# ledecorator-core-board.net
KiCad netlist of a schematic drawn in EAGLE
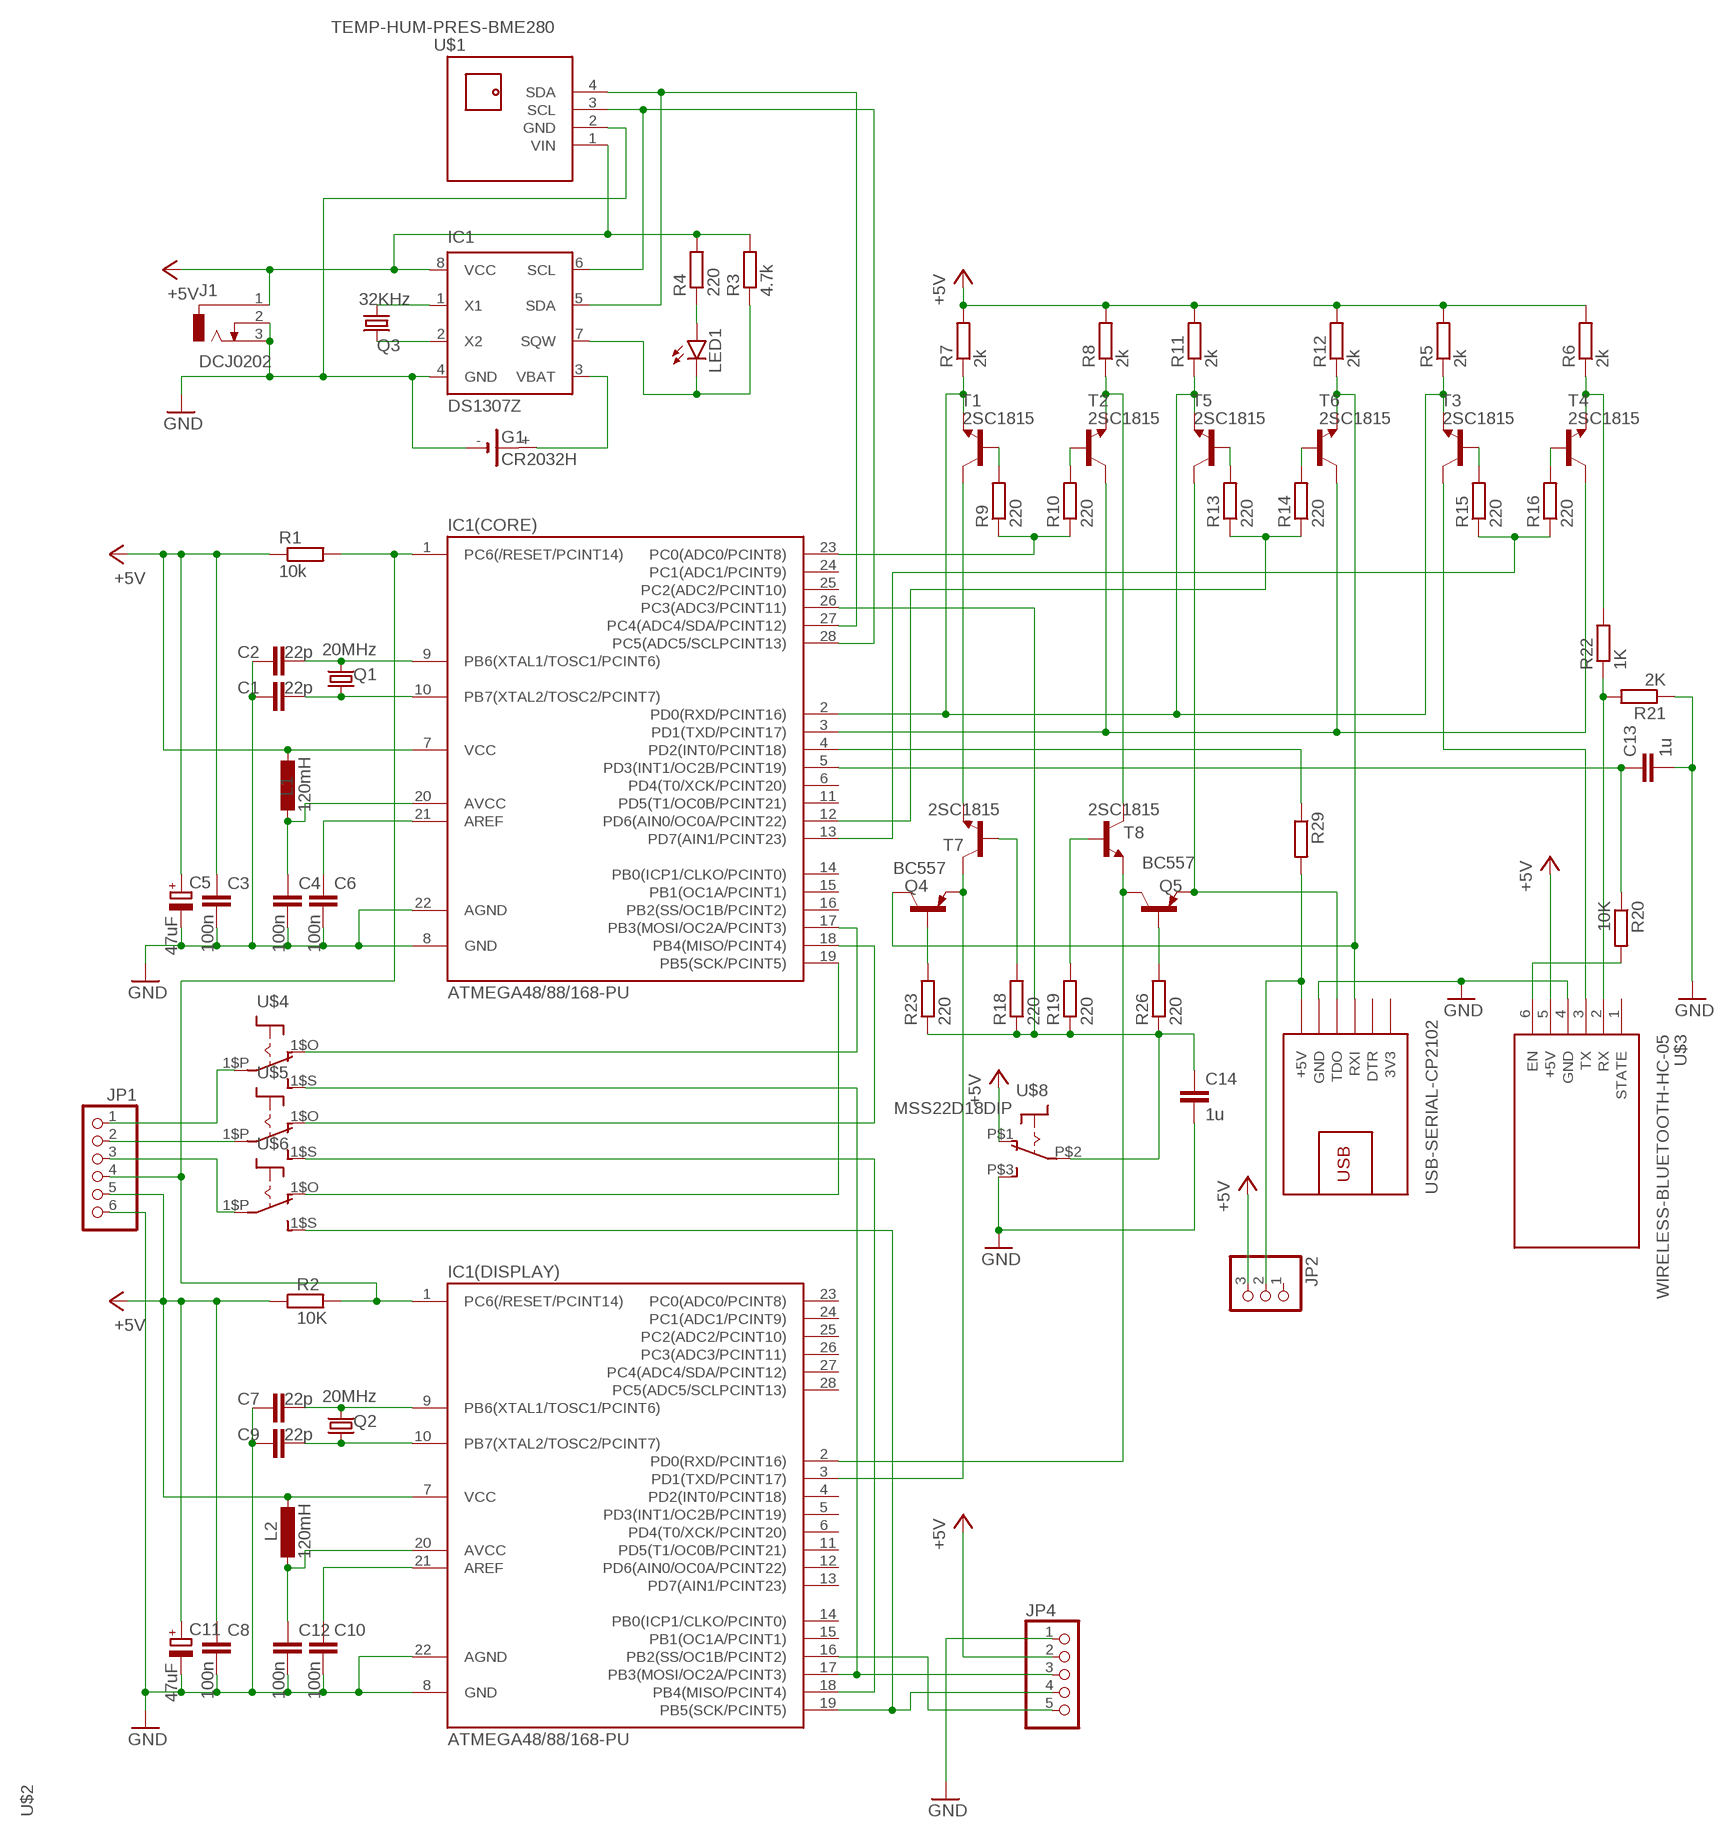
[diagram p0: schematic, sheet 1]

(export (version "E")
  (design (tool "Eeschema 10.0.6"))
  (components
    (comp (ref "C1")
      (value "22p")
      (footprint "eagle-import:C025-025X050")
      (libsource (lib "eagle-import") (part "C-EU025-025X050"))
    )
    (comp (ref "C2")
      (value "22p")
      (footprint "eagle-import:C025-025X050")
      (libsource (lib "eagle-import") (part "C-EU025-025X050"))
    )
    (comp (ref "C3")
      (value "100n")
      (footprint "eagle-import:C025-025X050")
      (libsource (lib "eagle-import") (part "C-EU025-025X050"))
    )
    (comp (ref "C4")
      (value "100n")
      (footprint "eagle-import:C1206")
      (libsource (lib "eagle-import") (part "C-EUC1206"))
    )
    (comp (ref "C5")
      (value "47uF")
      (footprint "eagle-import:E2-4")
      (libsource (lib "eagle-import") (part "CPOL-EUE2-4"))
    )
    (comp (ref "C6")
      (value "100n")
      (footprint "eagle-import:C1206")
      (libsource (lib "eagle-import") (part "C-EUC1206"))
    )
    (comp (ref "C7")
      (value "22p")
      (footprint "eagle-import:C025-025X050")
      (libsource (lib "eagle-import") (part "C-EU025-025X050"))
    )
    (comp (ref "C8")
      (value "100n")
      (footprint "eagle-import:C025-025X050")
      (libsource (lib "eagle-import") (part "C-EU025-025X050"))
    )
    (comp (ref "C9")
      (value "22p")
      (footprint "eagle-import:C025-025X050")
      (libsource (lib "eagle-import") (part "C-EU025-025X050"))
    )
    (comp (ref "C10")
      (value "100n")
      (footprint "eagle-import:C025-025X050")
      (libsource (lib "eagle-import") (part "C-EU025-025X050"))
    )
    (comp (ref "C11")
      (value "47uF")
      (footprint "eagle-import:E2-4")
      (libsource (lib "eagle-import") (part "CPOL-EUE2-4"))
    )
    (comp (ref "C12")
      (value "100n")
      (footprint "eagle-import:C025-025X050")
      (libsource (lib "eagle-import") (part "C-EU025-025X050"))
    )
    (comp (ref "C13")
      (value "1u")
      (footprint "eagle-import:C1206")
      (libsource (lib "eagle-import") (part "C-EUC1206"))
    )
    (comp (ref "C14")
      (value "1u")
      (footprint "eagle-import:C050-025X075")
      (libsource (lib "eagle-import") (part "C-EU050-025X075"))
    )
    (comp (ref "G1")
      (value "CR2032H")
      (footprint "eagle-import:CR2032H")
      (libsource (lib "eagle-import") (part "CR2032H"))
    )
    (comp (ref "IC1")
      (value "DS1307Z")
      (footprint "eagle-import:SOIC8")
      (libsource (lib "eagle-import") (part "DS1307Z"))
    )
    (comp (ref "IC1(CORE)")
      (value "ATMEGA48/88/168-PU")
      (footprint "eagle-import:DIL28-3")
      (libsource (lib "eagle-import") (part "ATMEGA48/88/168-PU"))
    )
    (comp (ref "IC1(DISPLAY)")
      (value "ATMEGA48/88/168-PU")
      (footprint "eagle-import:DIL28-3")
      (libsource (lib "eagle-import") (part "ATMEGA48/88/168-PU"))
    )
    (comp (ref "J1")
      (value "DCJ0202")
      (footprint "eagle-import:DCJ0202")
      (libsource (lib "eagle-import") (part "DCJ0202"))
    )
    (comp (ref "JP1")
      (value "PINHD-1X6/90")
      (footprint "eagle-import:1X06_90")
      (libsource (lib "eagle-import") (part "PINHD-1X6/90"))
    )
    (comp (ref "JP2")
      (value "PINHD-1X3/90")
      (footprint "eagle-import:1X03_90")
      (libsource (lib "eagle-import") (part "PINHD-1X3/90"))
    )
    (comp (ref "JP4")
      (value "PINHD-1X5")
      (footprint "eagle-import:1X05")
      (libsource (lib "eagle-import") (part "PINHD-1X5"))
    )
    (comp (ref "L1")
      (value "120mH")
      (footprint "eagle-import:0207_10")
      (libsource (lib "eagle-import") (part "L-EU0207/10"))
    )
    (comp (ref "L2")
      (value "120mH")
      (footprint "eagle-import:0207_10")
      (libsource (lib "eagle-import") (part "L-EU0207/10"))
    )
    (comp (ref "LED1")
      (value "LED3MM")
      (footprint "eagle-import:LED3MM")
      (libsource (lib "eagle-import") (part "LED3MM"))
    )
    (comp (ref "Q1")
      (value "20MHz")
      (footprint "eagle-import:HC49_S")
      (libsource (lib "eagle-import") (part "CRYSTALHC49S"))
    )
    (comp (ref "Q2")
      (value "20MHz")
      (footprint "eagle-import:HC49_S")
      (libsource (lib "eagle-import") (part "CRYSTALHC49S"))
    )
    (comp (ref "Q3")
      (value "32KHz")
      (footprint "eagle-import:TC26H")
      (libsource (lib "eagle-import") (part "CRYSTALTC26H"))
    )
    (comp (ref "Q4")
      (value "BC557")
      (footprint "eagle-import:TO92-EBC")
      (libsource (lib "eagle-import") (part "BC557"))
    )
    (comp (ref "Q5")
      (value "BC557")
      (footprint "eagle-import:TO92-EBC")
      (libsource (lib "eagle-import") (part "BC557"))
    )
    (comp (ref "R1")
      (value "10k")
      (footprint "eagle-import:0207_10")
      (libsource (lib "eagle-import") (part "rcl_334_R-EU_0207/10"))
    )
    (comp (ref "R2")
      (value "10K")
      (footprint "eagle-import:0207_10")
      (libsource (lib "eagle-import") (part "R-EU_0207/10"))
    )
    (comp (ref "R3")
      (value "4.7k")
      (footprint "eagle-import:R1206")
      (libsource (lib "eagle-import") (part "rcl_334_R-EU_R1206"))
    )
    (comp (ref "R4")
      (value "220")
      (footprint "eagle-import:R1206")
      (libsource (lib "eagle-import") (part "rcl_334_R-EU_R1206"))
    )
    (comp (ref "R5")
      (value "2k")
      (footprint "eagle-import:0207_12")
      (libsource (lib "eagle-import") (part "rcl_334_R-EU_0207/12"))
    )
    (comp (ref "R6")
      (value "2k")
      (footprint "eagle-import:0207_12")
      (libsource (lib "eagle-import") (part "rcl_334_R-EU_0207/12"))
    )
    (comp (ref "R7")
      (value "2k")
      (footprint "eagle-import:R1206")
      (libsource (lib "eagle-import") (part "rcl_334_R-EU_R1206"))
    )
    (comp (ref "R8")
      (value "2k")
      (footprint "eagle-import:R1206")
      (libsource (lib "eagle-import") (part "rcl_334_R-EU_R1206"))
    )
    (comp (ref "R9")
      (value "220")
      (footprint "eagle-import:0207_10")
      (libsource (lib "eagle-import") (part "rcl_334_R-EU_0207/10"))
    )
    (comp (ref "R10")
      (value "220")
      (footprint "eagle-import:0207_10")
      (libsource (lib "eagle-import") (part "rcl_334_R-EU_0207/10"))
    )
    (comp (ref "R11")
      (value "2k")
      (footprint "eagle-import:0207_12")
      (libsource (lib "eagle-import") (part "rcl_334_R-EU_0207/12"))
    )
    (comp (ref "R12")
      (value "2k")
      (footprint "eagle-import:0207_10")
      (libsource (lib "eagle-import") (part "rcl_334_R-EU_0207/10"))
    )
    (comp (ref "R13")
      (value "220")
      (footprint "eagle-import:0207_10")
      (libsource (lib "eagle-import") (part "rcl_334_R-EU_0207/10"))
    )
    (comp (ref "R14")
      (value "220")
      (footprint "eagle-import:0207_10")
      (libsource (lib "eagle-import") (part "rcl_334_R-EU_0207/10"))
    )
    (comp (ref "R15")
      (value "220")
      (footprint "eagle-import:0207_10")
      (libsource (lib "eagle-import") (part "rcl_334_R-EU_0207/10"))
    )
    (comp (ref "R16")
      (value "220")
      (footprint "eagle-import:0207_10")
      (libsource (lib "eagle-import") (part "rcl_334_R-EU_0207/10"))
    )
    (comp (ref "R18")
      (value "220")
      (footprint "eagle-import:0207_10")
      (libsource (lib "eagle-import") (part "rcl_334_R-EU_0207/10"))
    )
    (comp (ref "R19")
      (value "220")
      (footprint "eagle-import:0207_10")
      (libsource (lib "eagle-import") (part "rcl_334_R-EU_0207/10"))
    )
    (comp (ref "R20")
      (value "10K")
      (footprint "eagle-import:0207_10")
      (libsource (lib "eagle-import") (part "rcl_334_R-EU_0207/10"))
    )
    (comp (ref "R21")
      (value "2K")
      (footprint "eagle-import:0207_10")
      (libsource (lib "eagle-import") (part "rcl_334_R-EU_0207/10"))
    )
    (comp (ref "R22")
      (value "1K")
      (footprint "eagle-import:0207_10")
      (libsource (lib "eagle-import") (part "rcl_334_R-EU_0207/10"))
    )
    (comp (ref "R23")
      (value "220")
      (footprint "eagle-import:R1206")
      (libsource (lib "eagle-import") (part "rcl_334_R-EU_R1206"))
    )
    (comp (ref "R26")
      (value "220")
      (footprint "eagle-import:R1206")
      (libsource (lib "eagle-import") (part "rcl_334_R-EU_R1206"))
    )
    (comp (ref "R29")
      (value "R-EU_0207/10")
      (footprint "eagle-import:0207_10")
      (libsource (lib "eagle-import") (part "rcl_334_R-EU_0207/10"))
    )
    (comp (ref "T1")
      (value "2SC1815")
      (footprint "eagle-import:TO92-ECB")
      (libsource (lib "eagle-import") (part "2SC1815"))
    )
    (comp (ref "T2")
      (value "2SC1815")
      (footprint "eagle-import:TO92-ECB")
      (libsource (lib "eagle-import") (part "2SC1815"))
    )
    (comp (ref "T3")
      (value "2SC1815")
      (footprint "eagle-import:TO92-ECB")
      (libsource (lib "eagle-import") (part "2SC1815"))
    )
    (comp (ref "T4")
      (value "2SC1815")
      (footprint "eagle-import:TO92-ECB")
      (libsource (lib "eagle-import") (part "2SC1815"))
    )
    (comp (ref "T5")
      (value "2SC1815")
      (footprint "eagle-import:TO92-ECB")
      (libsource (lib "eagle-import") (part "2SC1815"))
    )
    (comp (ref "T6")
      (value "2SC1815")
      (footprint "eagle-import:TO92-ECB")
      (libsource (lib "eagle-import") (part "2SC1815"))
    )
    (comp (ref "T7")
      (value "2SC1815")
      (footprint "eagle-import:TO92-ECB")
      (libsource (lib "eagle-import") (part "2SC1815"))
    )
    (comp (ref "T8")
      (value "2SC1815")
      (footprint "eagle-import:TO92-ECB")
      (libsource (lib "eagle-import") (part "2SC1815"))
    )
    (comp (ref "U$1")
      (value "TEMP-HUM-PRES-BME280")
      (footprint "eagle-import:TEMP-HUM-PRES-BME280")
      (libsource (lib "eagle-import") (part "TEMP-HUM-PRES-BME280"))
    )
    (comp (ref "U$2")
      (value "USB-SERIAL-CP2102")
      (footprint "eagle-import:USB-SERIAL-CP2102")
      (libsource (lib "eagle-import") (part "USB-SERIAL-CP2102"))
    )
    (comp (ref "U$3")
      (value "WIRELESS-BLUETOOTH-HC-05")
      (footprint "eagle-import:WIRELESS-BLUETOOTH-HC-05")
      (libsource (lib "eagle-import") (part "WIRELESS-BLUETOOTH-HC-05"))
    )
    (comp (ref "U$4")
      (value "SS12D00DIP")
      (footprint "eagle-import:SS12D00")
      (libsource (lib "eagle-import") (part "SS12D00DIP"))
    )
    (comp (ref "U$5")
      (value "SS12D00DIP")
      (footprint "eagle-import:SS12D00")
      (libsource (lib "eagle-import") (part "SS12D00DIP"))
    )
    (comp (ref "U$6")
      (value "SS12D00DIP")
      (footprint "eagle-import:SS12D00")
      (libsource (lib "eagle-import") (part "SS12D00DIP"))
    )
    (comp (ref "U$8")
      (value "MSS22D18DIP")
      (footprint "eagle-import:MSS22D18")
      (libsource (lib "eagle-import") (part "MSS22D18DIP"))
    )
  )
  (nets
    (net (code "1") (name "+5V") (class "Default")
      (node (ref "C11") (pin "+") (pinfunction "+_+") (pintype "passive"))
      (node (ref "C3") (pin "1") (pinfunction "1_1") (pintype "passive"))
      (node (ref "C5") (pin "+") (pinfunction "+_+") (pintype "passive"))
      (node (ref "C8") (pin "1") (pinfunction "1_1") (pintype "passive"))
      (node (ref "IC1") (pin "8") (pinfunction "VCC_8") (pintype "power_in"))
      (node (ref "IC1(CORE)") (pin "7") (pinfunction "VCC_7") (pintype "power_in"))
      (node (ref "IC1(DISPLAY)") (pin "7") (pinfunction "VCC_7") (pintype "power_in"))
      (node (ref "J1") (pin "1") (pinfunction "1_1") (pintype "passive"))
      (node (ref "JP1") (pin "5") (pinfunction "5_5") (pintype "passive"))
      (node (ref "JP2") (pin "3") (pinfunction "3_3") (pintype "passive"))
      (node (ref "JP4") (pin "2") (pinfunction "2_2") (pintype "passive"))
      (node (ref "L1") (pin "1") (pinfunction "1_1") (pintype "passive"))
      (node (ref "L2") (pin "1") (pinfunction "1_1") (pintype "passive"))
      (node (ref "R1") (pin "1") (pinfunction "1_1") (pintype "passive"))
      (node (ref "R11") (pin "2") (pinfunction "2_2") (pintype "passive"))
      (node (ref "R12") (pin "2") (pinfunction "2_2") (pintype "passive"))
      (node (ref "R2") (pin "1") (pinfunction "1_1") (pintype "passive"))
      (node (ref "R3") (pin "2") (pinfunction "2_2") (pintype "passive"))
      (node (ref "R4") (pin "2") (pinfunction "2_2") (pintype "passive"))
      (node (ref "R5") (pin "2") (pinfunction "2_2") (pintype "passive"))
      (node (ref "R6") (pin "2") (pinfunction "2_2") (pintype "passive"))
      (node (ref "R7") (pin "2") (pinfunction "2_2") (pintype "passive"))
      (node (ref "R8") (pin "2") (pinfunction "2_2") (pintype "passive"))
      (node (ref "U$1") (pin "1") (pinfunction "VIN_1") (pintype "power_in"))
      (node (ref "U$3") (pin "5") (pinfunction "+5V_5") (pintype "power_in"))
      (node (ref "U$8") (pin "P$1") (pinfunction "O_P$1") (pintype "passive"))
    )
    (net (code "2") (name "/3V3") (class "Default")
      (node (ref "U$2") (pin "1") (pinfunction "3V3_1") (pintype "power_in"))
    )
    (net (code "3") (name "GND") (class "Default")
      (node (ref "C1") (pin "1") (pinfunction "1_1") (pintype "passive"))
      (node (ref "C10") (pin "2") (pinfunction "2_2") (pintype "passive"))
      (node (ref "C11") (pin "-") (pinfunction "-_-") (pintype "passive"))
      (node (ref "C12") (pin "2") (pinfunction "2_2") (pintype "passive"))
      (node (ref "C13") (pin "2") (pinfunction "2_2") (pintype "passive"))
      (node (ref "C14") (pin "2") (pinfunction "2_2") (pintype "passive"))
      (node (ref "C2") (pin "1") (pinfunction "1_1") (pintype "passive"))
      (node (ref "C3") (pin "2") (pinfunction "2_2") (pintype "passive"))
      (node (ref "C4") (pin "2") (pinfunction "2_2") (pintype "passive"))
      (node (ref "C5") (pin "-") (pinfunction "-_-") (pintype "passive"))
      (node (ref "C6") (pin "2") (pinfunction "2_2") (pintype "passive"))
      (node (ref "C7") (pin "1") (pinfunction "1_1") (pintype "passive"))
      (node (ref "C8") (pin "2") (pinfunction "2_2") (pintype "passive"))
      (node (ref "C9") (pin "1") (pinfunction "1_1") (pintype "passive"))
      (node (ref "G1") (pin "-") (pinfunction "-_-") (pintype "passive"))
      (node (ref "IC1") (pin "4") (pinfunction "GND_4") (pintype "power_in"))
      (node (ref "IC1(CORE)") (pin "22") (pinfunction "AGND_22") (pintype "power_in"))
      (node (ref "IC1(CORE)") (pin "8") (pinfunction "GND_8") (pintype "power_in"))
      (node (ref "IC1(DISPLAY)") (pin "22") (pinfunction "AGND_22") (pintype "power_in"))
      (node (ref "IC1(DISPLAY)") (pin "8") (pinfunction "GND_8") (pintype "power_in"))
      (node (ref "J1") (pin "2") (pinfunction "2_2") (pintype "passive"))
      (node (ref "J1") (pin "3") (pinfunction "3_3") (pintype "passive"))
      (node (ref "JP1") (pin "6") (pinfunction "6_6") (pintype "passive"))
      (node (ref "JP4") (pin "1") (pinfunction "1_1") (pintype "passive"))
      (node (ref "R21") (pin "1") (pinfunction "1_1") (pintype "passive"))
      (node (ref "U$1") (pin "2") (pinfunction "GND_2") (pintype "power_in"))
      (node (ref "U$2") (pin "5") (pinfunction "GND_5") (pintype "power_in"))
      (node (ref "U$3") (pin "4") (pinfunction "GND_4") (pintype "power_in"))
      (node (ref "U$8") (pin "P$3") (pinfunction "S_P$3") (pintype "passive"))
    )
    (net (code "4") (name "Net-(IC1(CORE)-AREF)") (class "Default")
      (node (ref "C6") (pin "1") (pinfunction "1_1") (pintype "passive"))
      (node (ref "IC1(CORE)") (pin "21") (pinfunction "AREF_21") (pintype "passive"))
    )
    (net (code "5") (name "Net-(IC1(CORE)-AVCC)") (class "Default")
      (node (ref "C4") (pin "1") (pinfunction "1_1") (pintype "passive"))
      (node (ref "IC1(CORE)") (pin "20") (pinfunction "AVCC_20") (pintype "passive"))
      (node (ref "L1") (pin "2") (pinfunction "2_2") (pintype "passive"))
    )
    (net (code "6") (name "Net-(IC1(CORE)-PB3(MOSI{slash}OC2A{slash}PCINT3))") (class "Default")
      (node (ref "IC1(CORE)") (pin "17") (pinfunction "PB3(MOSI/OC2A/PCINT3)_17") (pintype "bidirectional"))
      (node (ref "U$4") (pin "1$O") (pinfunction "O_1$O") (pintype "passive"))
    )
    (net (code "7") (name "Net-(IC1(CORE)-PB4(MISO{slash}PCINT4))") (class "Default")
      (node (ref "IC1(CORE)") (pin "18") (pinfunction "PB4(MISO/PCINT4)_18") (pintype "bidirectional"))
      (node (ref "U$5") (pin "1$O") (pinfunction "O_1$O") (pintype "passive"))
    )
    (net (code "8") (name "Net-(IC1(CORE)-PB5(SCK{slash}PCINT5))") (class "Default")
      (node (ref "IC1(CORE)") (pin "19") (pinfunction "PB5(SCK/PCINT5)_19") (pintype "bidirectional"))
      (node (ref "U$6") (pin "1$O") (pinfunction "O_1$O") (pintype "passive"))
    )
    (net (code "9") (name "Net-(IC1(CORE)-PB6(XTAL1{slash}TOSC1{slash}PCINT6))") (class "Default")
      (node (ref "C2") (pin "2") (pinfunction "2_2") (pintype "passive"))
      (node (ref "IC1(CORE)") (pin "9") (pinfunction "PB6(XTAL1/TOSC1/PCINT6)_9") (pintype "bidirectional"))
      (node (ref "Q1") (pin "2") (pinfunction "2_2") (pintype "passive"))
    )
    (net (code "10") (name "Net-(IC1(CORE)-PB7(XTAL2{slash}TOSC2{slash}PCINT7))") (class "Default")
      (node (ref "C1") (pin "2") (pinfunction "2_2") (pintype "passive"))
      (node (ref "IC1(CORE)") (pin "10") (pinfunction "PB7(XTAL2/TOSC2/PCINT7)_10") (pintype "bidirectional"))
      (node (ref "Q1") (pin "1") (pinfunction "1_1") (pintype "passive"))
    )
    (net (code "11") (name "Net-(IC1(CORE)-PC0(ADC0{slash}PCINT8))") (class "Default")
      (node (ref "IC1(CORE)") (pin "23") (pinfunction "PC0(ADC0/PCINT8)_23") (pintype "bidirectional"))
      (node (ref "R10") (pin "1") (pinfunction "1_1") (pintype "passive"))
      (node (ref "R9") (pin "1") (pinfunction "1_1") (pintype "passive"))
    )
    (net (code "12") (name "Net-(IC1(CORE)-PC3(ADC3{slash}PCINT11))") (class "Default")
      (node (ref "C14") (pin "1") (pinfunction "1_1") (pintype "passive"))
      (node (ref "IC1(CORE)") (pin "26") (pinfunction "PC3(ADC3/PCINT11)_26") (pintype "bidirectional"))
      (node (ref "R18") (pin "1") (pinfunction "1_1") (pintype "passive"))
      (node (ref "R19") (pin "1") (pinfunction "1_1") (pintype "passive"))
      (node (ref "R23") (pin "1") (pinfunction "1_1") (pintype "passive"))
      (node (ref "R26") (pin "1") (pinfunction "1_1") (pintype "passive"))
      (node (ref "U$8") (pin "P$2") (pinfunction "P_P$2") (pintype "passive"))
    )
    (net (code "13") (name "Net-(IC1(CORE)-PC4(ADC4{slash}SDA{slash}PCINT12))") (class "Default")
      (node (ref "IC1") (pin "5") (pinfunction "SDA_5") (pintype "bidirectional"))
      (node (ref "IC1(CORE)") (pin "27") (pinfunction "PC4(ADC4/SDA/PCINT12)_27") (pintype "bidirectional"))
      (node (ref "U$1") (pin "4") (pinfunction "SDA_4") (pintype "bidirectional"))
    )
    (net (code "14") (name "Net-(IC1(CORE)-PC5(ADC5{slash}SCLPCINT13))") (class "Default")
      (node (ref "IC1") (pin "6") (pinfunction "SCL_6") (pintype "input"))
      (node (ref "IC1(CORE)") (pin "28") (pinfunction "PC5(ADC5/SCLPCINT13)_28") (pintype "bidirectional"))
      (node (ref "U$1") (pin "3") (pinfunction "SCL_3") (pintype "bidirectional"))
    )
    (net (code "15") (name "Net-(IC1(CORE)-PC6({slash}RESET{slash}PCINT14))") (class "Default")
      (node (ref "IC1(CORE)") (pin "1") (pinfunction "PC6(/RESET/PCINT14)_1") (pintype "bidirectional"))
      (node (ref "IC1(DISPLAY)") (pin "1") (pinfunction "PC6(/RESET/PCINT14)_1") (pintype "bidirectional"))
      (node (ref "JP1") (pin "4") (pinfunction "4_4") (pintype "passive"))
      (node (ref "R1") (pin "2") (pinfunction "2_2") (pintype "passive"))
      (node (ref "R2") (pin "2") (pinfunction "2_2") (pintype "passive"))
    )
    (net (code "16") (name "Net-(IC1(CORE)-PD0(RXD{slash}PCINT16))") (class "Default")
      (node (ref "IC1(CORE)") (pin "2") (pinfunction "PD0(RXD/PCINT16)_2") (pintype "bidirectional"))
      (node (ref "R11") (pin "1") (pinfunction "1_1") (pintype "passive"))
      (node (ref "R5") (pin "1") (pinfunction "1_1") (pintype "passive"))
      (node (ref "R7") (pin "1") (pinfunction "1_1") (pintype "passive"))
      (node (ref "T1") (pin "E") (pinfunction "E_E") (pintype "passive"))
      (node (ref "T3") (pin "E") (pinfunction "E_E") (pintype "passive"))
      (node (ref "T5") (pin "E") (pinfunction "E_E") (pintype "passive"))
    )
    (net (code "17") (name "Net-(IC1(CORE)-PD1(TXD{slash}PCINT17))") (class "Default")
      (node (ref "IC1(CORE)") (pin "3") (pinfunction "PD1(TXD/PCINT17)_3") (pintype "bidirectional"))
      (node (ref "T2") (pin "C") (pinfunction "C_C") (pintype "passive"))
      (node (ref "T4") (pin "C") (pinfunction "C_C") (pintype "passive"))
      (node (ref "T6") (pin "C") (pinfunction "C_C") (pintype "passive"))
    )
    (net (code "18") (name "Net-(IC1(CORE)-PD2(INT0{slash}PCINT18))") (class "Default")
      (node (ref "IC1(CORE)") (pin "4") (pinfunction "PD2(INT0/PCINT18)_4") (pintype "bidirectional"))
      (node (ref "R29") (pin "1") (pinfunction "1_1") (pintype "passive"))
    )
    (net (code "19") (name "Net-(IC1(CORE)-PD3(INT1{slash}OC2B{slash}PCINT19))") (class "Default")
      (node (ref "C13") (pin "1") (pinfunction "1_1") (pintype "passive"))
      (node (ref "IC1(CORE)") (pin "5") (pinfunction "PD3(INT1/OC2B/PCINT19)_5") (pintype "bidirectional"))
      (node (ref "R20") (pin "1") (pinfunction "1_1") (pintype "passive"))
    )
    (net (code "20") (name "Net-(IC1(CORE)-PD6(AIN0{slash}OC0A{slash}PCINT22))") (class "Default")
      (node (ref "IC1(CORE)") (pin "12") (pinfunction "PD6(AIN0/OC0A/PCINT22)_12") (pintype "bidirectional"))
      (node (ref "R13") (pin "1") (pinfunction "1_1") (pintype "passive"))
      (node (ref "R14") (pin "1") (pinfunction "1_1") (pintype "passive"))
    )
    (net (code "21") (name "Net-(IC1(CORE)-PD7(AIN1{slash}PCINT23))") (class "Default")
      (node (ref "IC1(CORE)") (pin "13") (pinfunction "PD7(AIN1/PCINT23)_13") (pintype "bidirectional"))
      (node (ref "R15") (pin "1") (pinfunction "1_1") (pintype "passive"))
      (node (ref "R16") (pin "1") (pinfunction "1_1") (pintype "passive"))
    )
    (net (code "22") (name "Net-(IC1(DISPLAY)-AREF)") (class "Default")
      (node (ref "C10") (pin "1") (pinfunction "1_1") (pintype "passive"))
      (node (ref "IC1(DISPLAY)") (pin "21") (pinfunction "AREF_21") (pintype "passive"))
    )
    (net (code "23") (name "Net-(IC1(DISPLAY)-AVCC)") (class "Default")
      (node (ref "C12") (pin "1") (pinfunction "1_1") (pintype "passive"))
      (node (ref "IC1(DISPLAY)") (pin "20") (pinfunction "AVCC_20") (pintype "passive"))
      (node (ref "L2") (pin "2") (pinfunction "2_2") (pintype "passive"))
    )
    (net (code "24") (name "Net-(IC1(DISPLAY)-PB2(SS{slash}OC1B{slash}PCINT2))") (class "Default")
      (node (ref "IC1(DISPLAY)") (pin "16") (pinfunction "PB2(SS/OC1B/PCINT2)_16") (pintype "bidirectional"))
      (node (ref "JP4") (pin "5") (pinfunction "5_5") (pintype "passive"))
    )
    (net (code "25") (name "Net-(IC1(DISPLAY)-PB3(MOSI{slash}OC2A{slash}PCINT3))") (class "Default")
      (node (ref "IC1(DISPLAY)") (pin "17") (pinfunction "PB3(MOSI/OC2A/PCINT3)_17") (pintype "bidirectional"))
      (node (ref "JP4") (pin "3") (pinfunction "3_3") (pintype "passive"))
      (node (ref "U$4") (pin "1$S") (pinfunction "S_1$S") (pintype "passive"))
    )
    (net (code "26") (name "Net-(IC1(DISPLAY)-PB4(MISO{slash}PCINT4))") (class "Default")
      (node (ref "IC1(DISPLAY)") (pin "18") (pinfunction "PB4(MISO/PCINT4)_18") (pintype "bidirectional"))
      (node (ref "U$5") (pin "1$S") (pinfunction "S_1$S") (pintype "passive"))
    )
    (net (code "27") (name "Net-(IC1(DISPLAY)-PB5(SCK{slash}PCINT5))") (class "Default")
      (node (ref "IC1(DISPLAY)") (pin "19") (pinfunction "PB5(SCK/PCINT5)_19") (pintype "bidirectional"))
      (node (ref "JP4") (pin "4") (pinfunction "4_4") (pintype "passive"))
      (node (ref "U$6") (pin "1$S") (pinfunction "S_1$S") (pintype "passive"))
    )
    (net (code "28") (name "Net-(IC1(DISPLAY)-PB6(XTAL1{slash}TOSC1{slash}PCINT6))") (class "Default")
      (node (ref "C7") (pin "2") (pinfunction "2_2") (pintype "passive"))
      (node (ref "IC1(DISPLAY)") (pin "9") (pinfunction "PB6(XTAL1/TOSC1/PCINT6)_9") (pintype "bidirectional"))
      (node (ref "Q2") (pin "2") (pinfunction "2_2") (pintype "passive"))
    )
    (net (code "29") (name "Net-(IC1(DISPLAY)-PB7(XTAL2{slash}TOSC2{slash}PCINT7))") (class "Default")
      (node (ref "C9") (pin "2") (pinfunction "2_2") (pintype "passive"))
      (node (ref "IC1(DISPLAY)") (pin "10") (pinfunction "PB7(XTAL2/TOSC2/PCINT7)_10") (pintype "bidirectional"))
      (node (ref "Q2") (pin "1") (pinfunction "1_1") (pintype "passive"))
    )
    (net (code "30") (name "Net-(IC1(DISPLAY)-PD0(RXD{slash}PCINT16))") (class "Default")
      (node (ref "IC1(DISPLAY)") (pin "2") (pinfunction "PD0(RXD/PCINT16)_2") (pintype "bidirectional"))
      (node (ref "Q5") (pin "C") (pinfunction "C_C") (pintype "passive"))
      (node (ref "T8") (pin "E") (pinfunction "E_E") (pintype "passive"))
    )
    (net (code "31") (name "Net-(IC1(DISPLAY)-PD1(TXD{slash}PCINT17))") (class "Default")
      (node (ref "IC1(DISPLAY)") (pin "3") (pinfunction "PD1(TXD/PCINT17)_3") (pintype "bidirectional"))
      (node (ref "Q4") (pin "E") (pinfunction "E_E") (pintype "passive"))
      (node (ref "T7") (pin "C") (pinfunction "C_C") (pintype "passive"))
    )
    (net (code "32") (name "Net-(IC1-SQW)") (class "Default")
      (node (ref "IC1") (pin "7") (pinfunction "SQW_7") (pintype "open_collector"))
      (node (ref "LED1") (pin "K") (pinfunction "C_K") (pintype "passive"))
      (node (ref "R3") (pin "1") (pinfunction "1_1") (pintype "passive"))
    )
    (net (code "33") (name "Net-(IC1-VBAT)") (class "Default")
      (node (ref "G1") (pin "+") (pinfunction "+_+") (pintype "passive"))
      (node (ref "IC1") (pin "3") (pinfunction "VBAT_3") (pintype "passive"))
    )
    (net (code "34") (name "Net-(IC1-X1)") (class "Default")
      (node (ref "IC1") (pin "1") (pinfunction "X1_1") (pintype "input"))
      (node (ref "Q3") (pin "1") (pinfunction "1_1") (pintype "passive"))
    )
    (net (code "35") (name "Net-(IC1-X2)") (class "Default")
      (node (ref "IC1") (pin "2") (pinfunction "X2_2") (pintype "output"))
      (node (ref "Q3") (pin "2") (pinfunction "2_2") (pintype "passive"))
    )
    (net (code "36") (name "Net-(LED1-PadA)") (class "Default")
      (node (ref "LED1") (pin "A") (pinfunction "A_A") (pintype "passive"))
      (node (ref "R4") (pin "1") (pinfunction "1_1") (pintype "passive"))
    )
    (net (code "37") (name "Net-(Q4-PadB)") (class "Default")
      (node (ref "Q4") (pin "B") (pinfunction "B_B") (pintype "passive"))
      (node (ref "R23") (pin "2") (pinfunction "2_2") (pintype "passive"))
    )
    (net (code "38") (name "Net-(Q5-PadB)") (class "Default")
      (node (ref "Q5") (pin "B") (pinfunction "B_B") (pintype "passive"))
      (node (ref "R26") (pin "2") (pinfunction "2_2") (pintype "passive"))
    )
    (net (code "39") (name "Net-(R8-Pad1)") (class "Default")
      (node (ref "R8") (pin "1") (pinfunction "1_1") (pintype "passive"))
      (node (ref "T2") (pin "E") (pinfunction "E_E") (pintype "passive"))
      (node (ref "T8") (pin "C") (pinfunction "C_C") (pintype "passive"))
    )
    (net (code "40") (name "Net-(R9-Pad2)") (class "Default")
      (node (ref "R9") (pin "2") (pinfunction "2_2") (pintype "passive"))
      (node (ref "T1") (pin "B") (pinfunction "B_B") (pintype "passive"))
    )
    (net (code "41") (name "Net-(R10-Pad2)") (class "Default")
      (node (ref "R10") (pin "2") (pinfunction "2_2") (pintype "passive"))
      (node (ref "T2") (pin "B") (pinfunction "B_B") (pintype "passive"))
    )
    (net (code "42") (name "Net-(R13-Pad2)") (class "Default")
      (node (ref "R13") (pin "2") (pinfunction "2_2") (pintype "passive"))
      (node (ref "T5") (pin "B") (pinfunction "B_B") (pintype "passive"))
    )
    (net (code "43") (name "Net-(R14-Pad2)") (class "Default")
      (node (ref "R14") (pin "2") (pinfunction "2_2") (pintype "passive"))
      (node (ref "T6") (pin "B") (pinfunction "B_B") (pintype "passive"))
    )
    (net (code "44") (name "Net-(R15-Pad2)") (class "Default")
      (node (ref "R15") (pin "2") (pinfunction "2_2") (pintype "passive"))
      (node (ref "T3") (pin "B") (pinfunction "B_B") (pintype "passive"))
    )
    (net (code "45") (name "Net-(R16-Pad2)") (class "Default")
      (node (ref "R16") (pin "2") (pinfunction "2_2") (pintype "passive"))
      (node (ref "T4") (pin "B") (pinfunction "B_B") (pintype "passive"))
    )
    (net (code "46") (name "Net-(R18-Pad2)") (class "Default")
      (node (ref "R18") (pin "2") (pinfunction "2_2") (pintype "passive"))
      (node (ref "T7") (pin "B") (pinfunction "B_B") (pintype "passive"))
    )
    (net (code "47") (name "Net-(R19-Pad2)") (class "Default")
      (node (ref "R19") (pin "2") (pinfunction "2_2") (pintype "passive"))
      (node (ref "T8") (pin "B") (pinfunction "B_B") (pintype "passive"))
    )
    (net (code "48") (name "Net-(R22-Pad2)") (class "Default")
      (node (ref "R22") (pin "2") (pinfunction "2_2") (pintype "passive"))
      (node (ref "R6") (pin "1") (pinfunction "1_1") (pintype "passive"))
      (node (ref "T4") (pin "E") (pinfunction "E_E") (pintype "passive"))
    )
    (net (code "49") (name "Net-(T1-PadC)") (class "Default")
      (node (ref "T1") (pin "C") (pinfunction "C_C") (pintype "passive"))
      (node (ref "T7") (pin "E") (pinfunction "E_E") (pintype "passive"))
    )
    (net (code "50") (name "Net-(U$2-+5V)") (class "Default")
      (node (ref "JP2") (pin "2") (pinfunction "2_2") (pintype "passive"))
      (node (ref "R29") (pin "2") (pinfunction "2_2") (pintype "passive"))
      (node (ref "U$2") (pin "6") (pinfunction "+5V_6") (pintype "power_in"))
    )
    (net (code "51") (name "Net-(U$2-RXI)") (class "Default")
      (node (ref "Q4") (pin "C") (pinfunction "C_C") (pintype "passive"))
      (node (ref "R12") (pin "1") (pinfunction "1_1") (pintype "passive"))
      (node (ref "T6") (pin "E") (pinfunction "E_E") (pintype "passive"))
      (node (ref "U$2") (pin "3") (pinfunction "RXI_3") (pintype "bidirectional"))
    )
    (net (code "52") (name "Net-(U$2-TDO)") (class "Default")
      (node (ref "Q5") (pin "E") (pinfunction "E_E") (pintype "passive"))
      (node (ref "T5") (pin "C") (pinfunction "C_C") (pintype "passive"))
      (node (ref "U$2") (pin "4") (pinfunction "TDO_4") (pintype "bidirectional"))
    )
    (net (code "53") (name "Net-(U$3-EN)") (class "Default")
      (node (ref "R20") (pin "2") (pinfunction "2_2") (pintype "passive"))
      (node (ref "U$3") (pin "6") (pinfunction "EN_6") (pintype "bidirectional"))
    )
    (net (code "54") (name "Net-(U$3-RX)") (class "Default")
      (node (ref "R21") (pin "2") (pinfunction "2_2") (pintype "passive"))
      (node (ref "R22") (pin "1") (pinfunction "1_1") (pintype "passive"))
      (node (ref "U$3") (pin "2") (pinfunction "RX_2") (pintype "bidirectional"))
    )
    (net (code "55") (name "Net-(U$3-TX)") (class "Default")
      (node (ref "T3") (pin "C") (pinfunction "C_C") (pintype "passive"))
      (node (ref "U$3") (pin "3") (pinfunction "TX_3") (pintype "bidirectional"))
    )
    (net (code "56") (name "Net-(U$4-P)") (class "Default")
      (node (ref "JP1") (pin "1") (pinfunction "1_1") (pintype "passive"))
      (node (ref "U$4") (pin "1$P") (pinfunction "P_1$P") (pintype "passive"))
    )
    (net (code "57") (name "Net-(U$5-P)") (class "Default")
      (node (ref "JP1") (pin "2") (pinfunction "2_2") (pintype "passive"))
      (node (ref "U$5") (pin "1$P") (pinfunction "P_1$P") (pintype "passive"))
    )
    (net (code "58") (name "Net-(U$6-P)") (class "Default")
      (node (ref "JP1") (pin "3") (pinfunction "3_3") (pintype "passive"))
      (node (ref "U$6") (pin "1$P") (pinfunction "P_1$P") (pintype "passive"))
    )
    (net (code "59") (name "unconnected-(IC1(CORE)-PB0(ICP1{slash}CLKO{slash}PCINT0)-Pad14)") (class "Default")
      (node (ref "IC1(CORE)") (pin "14") (pinfunction "PB0(ICP1/CLKO/PCINT0)_14") (pintype "bidirectional"))
    )
    (net (code "60") (name "unconnected-(IC1(CORE)-PB1(OC1A{slash}PCINT1)-Pad15)") (class "Default")
      (node (ref "IC1(CORE)") (pin "15") (pinfunction "PB1(OC1A/PCINT1)_15") (pintype "bidirectional"))
    )
    (net (code "61") (name "unconnected-(IC1(CORE)-PB2(SS{slash}OC1B{slash}PCINT2)-Pad16)") (class "Default")
      (node (ref "IC1(CORE)") (pin "16") (pinfunction "PB2(SS/OC1B/PCINT2)_16") (pintype "bidirectional"))
    )
    (net (code "62") (name "unconnected-(IC1(CORE)-PC1(ADC1{slash}PCINT9)-Pad24)") (class "Default")
      (node (ref "IC1(CORE)") (pin "24") (pinfunction "PC1(ADC1/PCINT9)_24") (pintype "bidirectional"))
    )
    (net (code "63") (name "unconnected-(IC1(CORE)-PC2(ADC2{slash}PCINT10)-Pad25)") (class "Default")
      (node (ref "IC1(CORE)") (pin "25") (pinfunction "PC2(ADC2/PCINT10)_25") (pintype "bidirectional"))
    )
    (net (code "64") (name "unconnected-(IC1(CORE)-PD4(T0{slash}XCK{slash}PCINT20)-Pad6)") (class "Default")
      (node (ref "IC1(CORE)") (pin "6") (pinfunction "PD4(T0/XCK/PCINT20)_6") (pintype "bidirectional"))
    )
    (net (code "65") (name "unconnected-(IC1(CORE)-PD5(T1{slash}OC0B{slash}PCINT21)-Pad11)") (class "Default")
      (node (ref "IC1(CORE)") (pin "11") (pinfunction "PD5(T1/OC0B/PCINT21)_11") (pintype "bidirectional"))
    )
    (net (code "66") (name "unconnected-(IC1(DISPLAY)-PB0(ICP1{slash}CLKO{slash}PCINT0)-Pad14)") (class "Default")
      (node (ref "IC1(DISPLAY)") (pin "14") (pinfunction "PB0(ICP1/CLKO/PCINT0)_14") (pintype "bidirectional"))
    )
    (net (code "67") (name "unconnected-(IC1(DISPLAY)-PB1(OC1A{slash}PCINT1)-Pad15)") (class "Default")
      (node (ref "IC1(DISPLAY)") (pin "15") (pinfunction "PB1(OC1A/PCINT1)_15") (pintype "bidirectional"))
    )
    (net (code "68") (name "unconnected-(IC1(DISPLAY)-PC0(ADC0{slash}PCINT8)-Pad23)") (class "Default")
      (node (ref "IC1(DISPLAY)") (pin "23") (pinfunction "PC0(ADC0/PCINT8)_23") (pintype "bidirectional"))
    )
    (net (code "69") (name "unconnected-(IC1(DISPLAY)-PC1(ADC1{slash}PCINT9)-Pad24)") (class "Default")
      (node (ref "IC1(DISPLAY)") (pin "24") (pinfunction "PC1(ADC1/PCINT9)_24") (pintype "bidirectional"))
    )
    (net (code "70") (name "unconnected-(IC1(DISPLAY)-PC2(ADC2{slash}PCINT10)-Pad25)") (class "Default")
      (node (ref "IC1(DISPLAY)") (pin "25") (pinfunction "PC2(ADC2/PCINT10)_25") (pintype "bidirectional"))
    )
    (net (code "71") (name "unconnected-(IC1(DISPLAY)-PC3(ADC3{slash}PCINT11)-Pad26)") (class "Default")
      (node (ref "IC1(DISPLAY)") (pin "26") (pinfunction "PC3(ADC3/PCINT11)_26") (pintype "bidirectional"))
    )
    (net (code "72") (name "unconnected-(IC1(DISPLAY)-PC4(ADC4{slash}SDA{slash}PCINT12)-Pad27)") (class "Default")
      (node (ref "IC1(DISPLAY)") (pin "27") (pinfunction "PC4(ADC4/SDA/PCINT12)_27") (pintype "bidirectional"))
    )
    (net (code "73") (name "unconnected-(IC1(DISPLAY)-PC5(ADC5{slash}SCLPCINT13)-Pad28)") (class "Default")
      (node (ref "IC1(DISPLAY)") (pin "28") (pinfunction "PC5(ADC5/SCLPCINT13)_28") (pintype "bidirectional"))
    )
    (net (code "74") (name "unconnected-(IC1(DISPLAY)-PD2(INT0{slash}PCINT18)-Pad4)") (class "Default")
      (node (ref "IC1(DISPLAY)") (pin "4") (pinfunction "PD2(INT0/PCINT18)_4") (pintype "bidirectional"))
    )
    (net (code "75") (name "unconnected-(IC1(DISPLAY)-PD3(INT1{slash}OC2B{slash}PCINT19)-Pad5)") (class "Default")
      (node (ref "IC1(DISPLAY)") (pin "5") (pinfunction "PD3(INT1/OC2B/PCINT19)_5") (pintype "bidirectional"))
    )
    (net (code "76") (name "unconnected-(IC1(DISPLAY)-PD4(T0{slash}XCK{slash}PCINT20)-Pad6)") (class "Default")
      (node (ref "IC1(DISPLAY)") (pin "6") (pinfunction "PD4(T0/XCK/PCINT20)_6") (pintype "bidirectional"))
    )
    (net (code "77") (name "unconnected-(IC1(DISPLAY)-PD5(T1{slash}OC0B{slash}PCINT21)-Pad11)") (class "Default")
      (node (ref "IC1(DISPLAY)") (pin "11") (pinfunction "PD5(T1/OC0B/PCINT21)_11") (pintype "bidirectional"))
    )
    (net (code "78") (name "unconnected-(IC1(DISPLAY)-PD6(AIN0{slash}OC0A{slash}PCINT22)-Pad12)") (class "Default")
      (node (ref "IC1(DISPLAY)") (pin "12") (pinfunction "PD6(AIN0/OC0A/PCINT22)_12") (pintype "bidirectional"))
    )
    (net (code "79") (name "unconnected-(IC1(DISPLAY)-PD7(AIN1{slash}PCINT23)-Pad13)") (class "Default")
      (node (ref "IC1(DISPLAY)") (pin "13") (pinfunction "PD7(AIN1/PCINT23)_13") (pintype "bidirectional"))
    )
    (net (code "80") (name "unconnected-(JP2-Pad1)") (class "Default")
      (node (ref "JP2") (pin "1") (pinfunction "1_1") (pintype "passive"))
    )
    (net (code "81") (name "unconnected-(U$2-DTR-Pad2)") (class "Default")
      (node (ref "U$2") (pin "2") (pinfunction "DTR_2") (pintype "bidirectional"))
    )
    (net (code "82") (name "unconnected-(U$3-STATE-Pad1)") (class "Default")
      (node (ref "U$3") (pin "1") (pinfunction "STATE_1") (pintype "bidirectional"))
    )
  )
)
